# Bolt.net
KiCad netlist of a schematic drawn in EAGLE
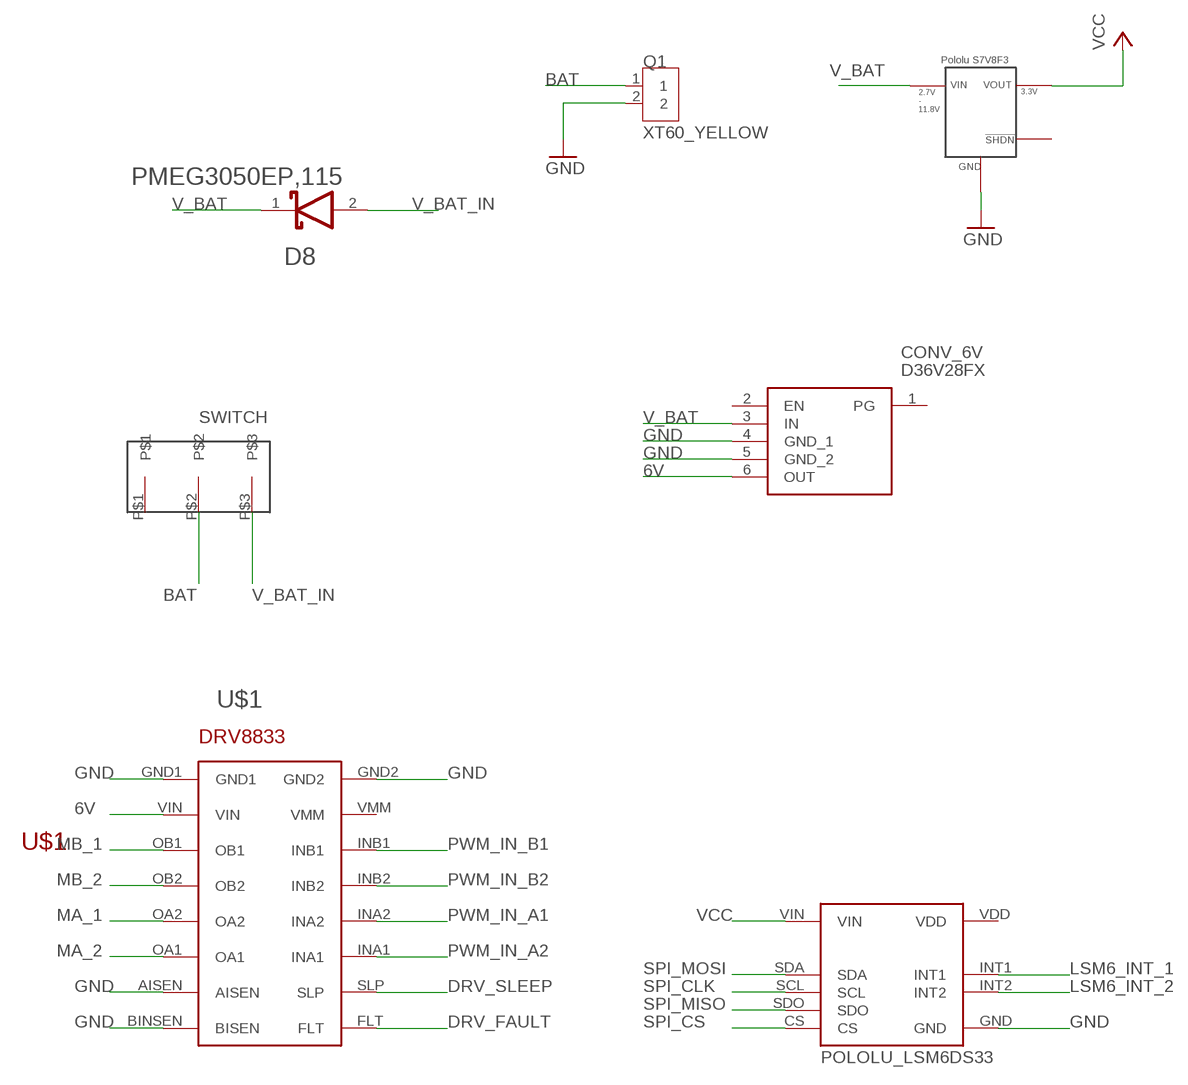
[diagram p0: schematic, sheet 1]
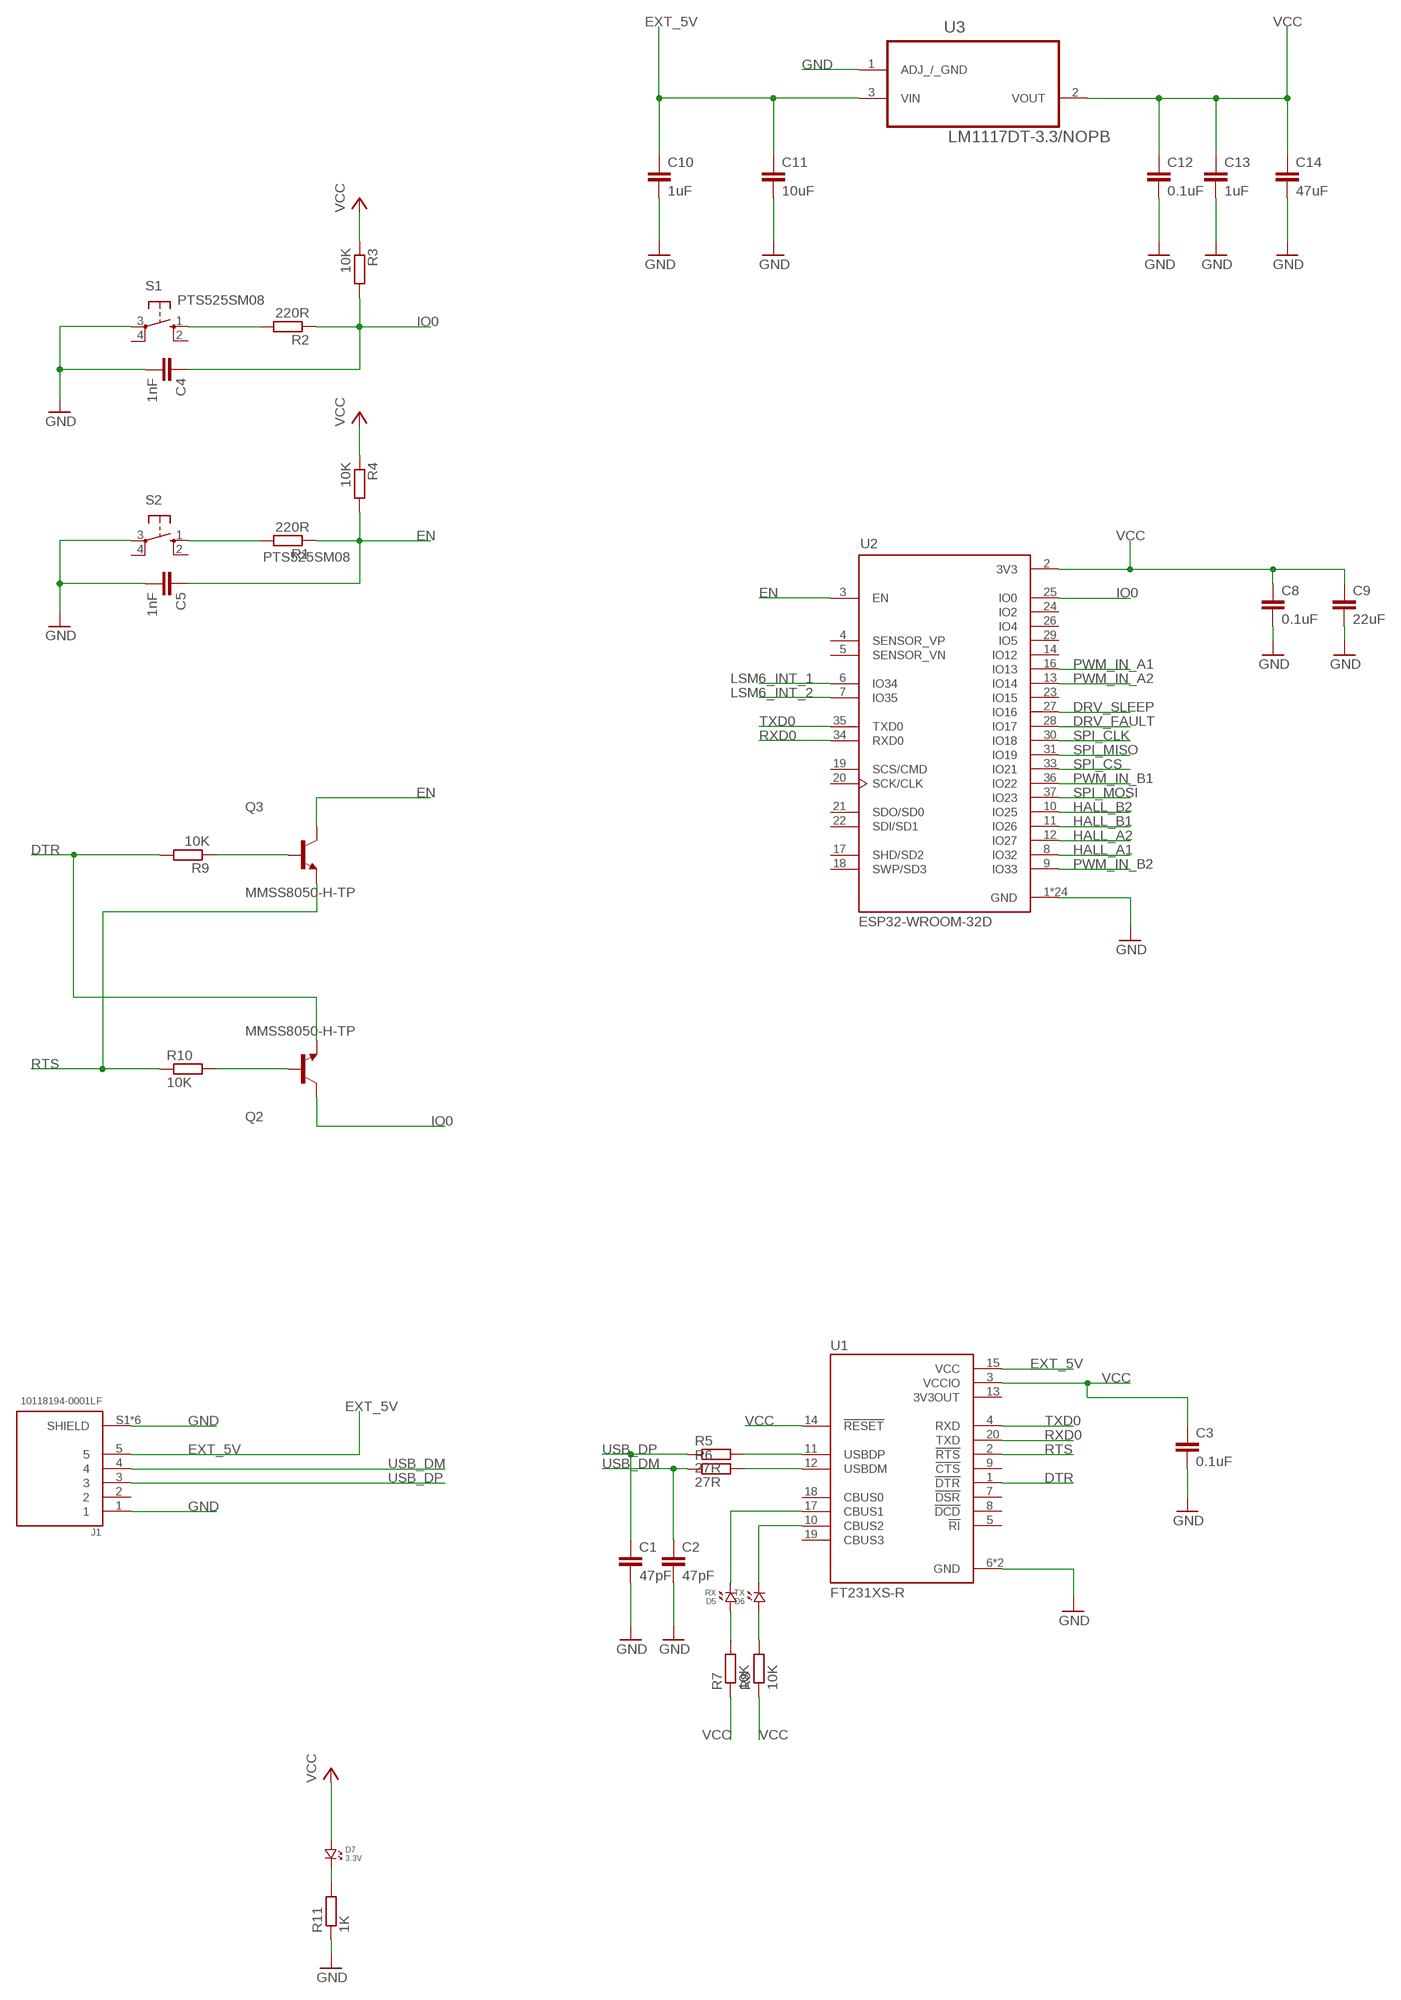
[diagram p1: schematic, sheet 2]
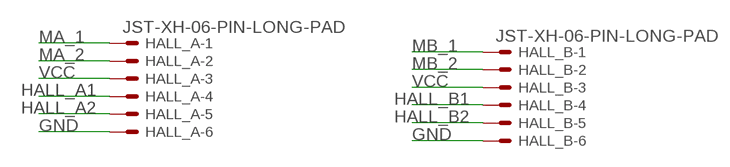
[diagram p2: schematic, sheet 3]

(export (version "E")
  (design (tool "Eeschema 10.0.6"))
  (components
    (comp (ref "HALL_A")
      (value "JST-XH-06-PIN-LONG-PAD")
      (footprint "eagle-import:JST-XH-06-PACKAGE-LONG-PAD")
      (libsource (lib "eagle-import") (part "JST-XH-06-PIN-LONG-PAD"))
    )
    (comp (ref "HALL_B")
      (value "JST-XH-06-PIN-LONG-PAD")
      (footprint "eagle-import:JST-XH-06-PACKAGE-LONG-PAD")
      (libsource (lib "eagle-import") (part "JST-XH-06-PIN-LONG-PAD"))
    )
    (comp (ref "CONV_3V3")
      (value "S7V8F3")
      (footprint "eagle-import:S7V8F3")
      (libsource (lib "eagle-import") (part "S7V8F3"))
    )
    (comp (ref "CONV_6V")
      (value "D36V28FX")
      (footprint "eagle-import:D36V28FX")
      (libsource (lib "eagle-import") (part "D36V28FX"))
    )
    (comp (ref "D8")
      (value "NEXPERIA_PMEG3050EP,115NEXPERIA_PMEG3050EP,115_0_0")
      (footprint "eagle-import:NEXPERIA_PMEG3050EP,115_0")
      (fields
        (field (name "DIGIKEY_PART_NUMBER") "1727-5317-1-ND")
        (field (name "MF") "Nexperia")
        (field (name "MOUSER_PART_NUMBER") "771-PMEG3050EP115")
      )
      (libsource (lib "eagle-import") (part "NEXPERIA_PMEG3050EP,115NEXPERIA_PMEG3050EP,115_0_0"))
    )
    (comp (ref "Q1")
      (value "XT60_YELLOW")
      (footprint "eagle-import:AMASS_XT60PB-M")
      (fields (field (name "MF") "Pololu") (field (name "MP") "XT60 YELLOW"))
      (libsource (lib "eagle-import") (part "XT60_YELLOW"))
    )
    (comp (ref "U$1")
      (value "POLOLU-DRV8833")
      (footprint "eagle-import:POLOLU-DRV8833")
      (libsource (lib "eagle-import") (part "POLOLU-DRV8833"))
    )
    (comp (ref "U$2")
      (value "POLOLU_LSM6DS33")
      (footprint "eagle-import:POLOLU_LSM6DS33")
      (libsource (lib "eagle-import") (part "POLOLU_LSM6DS33"))
    )
    (comp (ref "U$3")
      (value "SWITCH")
      (footprint "eagle-import:SWITCH")
      (libsource (lib "eagle-import") (part "SWITCH"))
    )
    (comp (ref "C1")
      (value "47pF")
      (footprint "eagle-import:C0805K")
      (libsource (lib "eagle-import") (part "C-EUC0805K"))
    )
    (comp (ref "C2")
      (value "47pF")
      (footprint "eagle-import:C0805K")
      (libsource (lib "eagle-import") (part "C-EUC0805K"))
    )
    (comp (ref "C3")
      (value "0.1uF")
      (footprint "eagle-import:C0805K")
      (libsource (lib "eagle-import") (part "C-EUC0805K"))
    )
    (comp (ref "C4")
      (value "1nF")
      (footprint "eagle-import:C0805K")
      (libsource (lib "eagle-import") (part "C-EUC0805K"))
    )
    (comp (ref "C5")
      (value "1nF")
      (footprint "eagle-import:C0805K")
      (libsource (lib "eagle-import") (part "C-EUC0805K"))
    )
    (comp (ref "C8")
      (value "0.1uF")
      (footprint "eagle-import:C0805K")
      (libsource (lib "eagle-import") (part "C-EUC0805K"))
    )
    (comp (ref "C9")
      (value "22uF")
      (footprint "eagle-import:C0805K")
      (libsource (lib "eagle-import") (part "C-EUC0805K"))
    )
    (comp (ref "C10")
      (value "1uF")
      (footprint "eagle-import:C0805K")
      (libsource (lib "eagle-import") (part "C-EUC0805K"))
    )
    (comp (ref "C11")
      (value "10uF")
      (footprint "eagle-import:C0805K")
      (libsource (lib "eagle-import") (part "C-EUC0805K"))
    )
    (comp (ref "C12")
      (value "0.1uF")
      (footprint "eagle-import:C0805K")
      (libsource (lib "eagle-import") (part "C-EUC0805K"))
    )
    (comp (ref "C13")
      (value "1uF")
      (footprint "eagle-import:C0805K")
      (libsource (lib "eagle-import") (part "C-EUC0805K"))
    )
    (comp (ref "C14")
      (value "47uF")
      (footprint "eagle-import:C0805K")
      (libsource (lib "eagle-import") (part "C-EUC0805K"))
    )
    (comp (ref "D5")
      (value "RX")
      (footprint "eagle-import:0805.LED")
      (libsource (lib "eagle-import") (part "LED.0805"))
    )
    (comp (ref "D6")
      (value "TX")
      (footprint "eagle-import:0805.LED")
      (libsource (lib "eagle-import") (part "LED.0805"))
    )
    (comp (ref "D7")
      (value "3.3V")
      (footprint "eagle-import:0805.LED")
      (libsource (lib "eagle-import") (part "LED.0805"))
    )
    (comp (ref "J1")
      (value "10118194-0001LF")
      (footprint "eagle-import:AMPHENOL_10118194-0001LF")
      (fields (field (name "MF") "Amphenol ICC (FCI)"))
      (libsource (lib "eagle-import") (part "10118194-0001LF"))
    )
    (comp (ref "Q2")
      (value "MMSS8050-H-TP")
      (footprint "eagle-import:TRANS_MMSS8050-H-TP")
      (fields (field (name "MF") "Micro Commercial"))
      (libsource (lib "eagle-import") (part "MMSS8050-H-TP"))
    )
    (comp (ref "Q3")
      (value "MMSS8050-H-TP")
      (footprint "eagle-import:TRANS_MMSS8050-H-TP")
      (fields (field (name "MF") "Micro Commercial"))
      (libsource (lib "eagle-import") (part "MMSS8050-H-TP"))
    )
    (comp (ref "R1")
      (value "220R")
      (footprint "eagle-import:R0805")
      (libsource (lib "eagle-import") (part "R-EU_R0805"))
    )
    (comp (ref "R2")
      (value "220R")
      (footprint "eagle-import:R0805")
      (libsource (lib "eagle-import") (part "R-EU_R0805"))
    )
    (comp (ref "R3")
      (value "10K")
      (footprint "eagle-import:R0805")
      (libsource (lib "eagle-import") (part "R-EU_R0805"))
    )
    (comp (ref "R4")
      (value "10K")
      (footprint "eagle-import:R0805")
      (libsource (lib "eagle-import") (part "R-EU_R0805"))
    )
    (comp (ref "R5")
      (value "27R")
      (footprint "eagle-import:R0805")
      (libsource (lib "eagle-import") (part "R-EU_R0805"))
    )
    (comp (ref "R6")
      (value "27R")
      (footprint "eagle-import:R0805")
      (libsource (lib "eagle-import") (part "R-EU_R0805"))
    )
    (comp (ref "R7")
      (value "10K")
      (footprint "eagle-import:R0805")
      (libsource (lib "eagle-import") (part "R-EU_R0805"))
    )
    (comp (ref "R8")
      (value "10K")
      (footprint "eagle-import:R0805")
      (libsource (lib "eagle-import") (part "R-EU_R0805"))
    )
    (comp (ref "R9")
      (value "10K")
      (footprint "eagle-import:R0805")
      (libsource (lib "eagle-import") (part "R-EU_R0805"))
    )
    (comp (ref "R10")
      (value "10K")
      (footprint "eagle-import:R0805")
      (libsource (lib "eagle-import") (part "R-EU_R0805"))
    )
    (comp (ref "R11")
      (value "1K")
      (footprint "eagle-import:R0805")
      (libsource (lib "eagle-import") (part "R-EU_R0805"))
    )
    (comp (ref "S1")
      (value "PTS525SM08")
      (footprint "eagle-import:SM08")
      (fields (field (name "MF") "C&K Components") (field (name "MPN") "PTS525SM08SMTR2LFS"))
      (libsource (lib "eagle-import") (part "PTS52508SM"))
    )
    (comp (ref "S2")
      (value "PTS525SM08")
      (footprint "eagle-import:SM08")
      (fields (field (name "MF") "C&K Components") (field (name "MPN") "PTS525SM08SMTR2LFS"))
      (libsource (lib "eagle-import") (part "PTS52508SM"))
    )
    (comp (ref "U1")
      (value "FT231XS-R")
      (footprint "eagle-import:SOP63P599X175-20N")
      (fields (field (name "DIGI-KEY_PART_NUMBER") "768-1129-1-ND") (field (name "MF") "FTDI,"))
      (libsource (lib "eagle-import") (part "FT231XS-R"))
    )
    (comp (ref "U2")
      (value "ESP32-WROOM-32D")
      (footprint "eagle-import:MODULE_ESP32-WROOM-32D")
      (fields (field (name "MF") "Espressif Systems"))
      (libsource (lib "eagle-import") (part "ESP32-WROOM-32D"))
    )
    (comp (ref "U3")
      (value "LM1117DT-3.3/NOPB")
      (footprint "eagle-import:TO228P970X238-3N")
      (fields (field (name "MF") "Texas Instruments"))
      (libsource (lib "eagle-import") (part "LM1117DT-3.3/NOPB"))
    )
  )
  (nets
    (net (code "1") (name "3V3OUT") (class "Default")
      (node (ref "U1") (pin "13") (pinfunction "3V3OUT_13") (pintype "power_in"))
    )
    (net (code "2") (name "6V") (class "Default")
      (node (ref "CONV_6V") (pin "6") (pinfunction "OUT_6") (pintype "bidirectional"))
      (node (ref "U$1") (pin "VIN") (pinfunction "VIN_VIN") (pintype "bidirectional"))
    )
    (net (code "3") (name "BAT") (class "Default")
      (node (ref "Q1") (pin "1") (pinfunction "1_1") (pintype "passive"))
      (node (ref "U$3") (pin "P$2") (pinfunction "P$2_P$2") (pintype "bidirectional"))
    )
    (net (code "4") (name "DRV_FAULT") (class "Default")
      (node (ref "U$1") (pin "FLT") (pinfunction "FLT_FLT") (pintype "bidirectional"))
      (node (ref "U2") (pin "28") (pinfunction "IO17_28") (pintype "bidirectional"))
    )
    (net (code "5") (name "DRV_SLEEP") (class "Default")
      (node (ref "U$1") (pin "SLP") (pinfunction "SLP_SLP") (pintype "bidirectional"))
      (node (ref "U2") (pin "27") (pinfunction "IO16_27") (pintype "bidirectional"))
    )
    (net (code "6") (name "DTR") (class "Default")
      (node (ref "Q2") (pin "2") (pinfunction "E_2") (pintype "passive"))
      (node (ref "R9") (pin "2") (pinfunction "2_2") (pintype "passive"))
      (node (ref "U1") (pin "1") (pinfunction "~{DTR}_1") (pintype "output"))
    )
    (net (code "7") (name "EN") (class "Default")
      (node (ref "C5") (pin "1") (pinfunction "1_1") (pintype "passive"))
      (node (ref "Q3") (pin "3") (pinfunction "C_3") (pintype "passive"))
      (node (ref "R1") (pin "1") (pinfunction "1_1") (pintype "passive"))
      (node (ref "R4") (pin "2") (pinfunction "2_2") (pintype "passive"))
      (node (ref "U2") (pin "3") (pinfunction "EN_3") (pintype "input"))
    )
    (net (code "8") (name "EXT_5V") (class "Default")
      (node (ref "C10") (pin "1") (pinfunction "1_1") (pintype "passive"))
      (node (ref "C11") (pin "1") (pinfunction "1_1") (pintype "passive"))
      (node (ref "J1") (pin "5") (pinfunction "5_5") (pintype "passive"))
      (node (ref "U1") (pin "15") (pinfunction "VCC_15") (pintype "power_in"))
      (node (ref "U3") (pin "3") (pinfunction "VIN_3") (pintype "input"))
    )
    (net (code "9") (name "GND") (class "Default")
      (node (ref "C1") (pin "2") (pinfunction "2_2") (pintype "passive"))
      (node (ref "C10") (pin "2") (pinfunction "2_2") (pintype "passive"))
      (node (ref "C11") (pin "2") (pinfunction "2_2") (pintype "passive"))
      (node (ref "C12") (pin "2") (pinfunction "2_2") (pintype "passive"))
      (node (ref "C13") (pin "2") (pinfunction "2_2") (pintype "passive"))
      (node (ref "C14") (pin "2") (pinfunction "2_2") (pintype "passive"))
      (node (ref "C2") (pin "2") (pinfunction "2_2") (pintype "passive"))
      (node (ref "C3") (pin "2") (pinfunction "2_2") (pintype "passive"))
      (node (ref "C4") (pin "2") (pinfunction "2_2") (pintype "passive"))
      (node (ref "C5") (pin "2") (pinfunction "2_2") (pintype "passive"))
      (node (ref "C8") (pin "2") (pinfunction "2_2") (pintype "passive"))
      (node (ref "C9") (pin "2") (pinfunction "2_2") (pintype "passive"))
      (node (ref "CONV_3V3") (pin "GND") (pinfunction "GND_GND") (pintype "bidirectional"))
      (node (ref "CONV_6V") (pin "4") (pinfunction "GND_1_4") (pintype "bidirectional"))
      (node (ref "CONV_6V") (pin "5") (pinfunction "GND_2_5") (pintype "bidirectional"))
      (node (ref "HALL_A") (pin "6") (pinfunction "S_6") (pintype "passive"))
      (node (ref "HALL_B") (pin "6") (pinfunction "S_6") (pintype "passive"))
      (node (ref "J1") (pin "1") (pinfunction "1_1") (pintype "passive"))
      (node (ref "J1") (pin "S1") (pinfunction "SHIELD_S1") (pintype "passive"))
      (node (ref "J1") (pin "S2") (pinfunction "SHIELD_S2") (pintype "passive"))
      (node (ref "J1") (pin "S3") (pinfunction "SHIELD_S3") (pintype "passive"))
      (node (ref "J1") (pin "S4") (pinfunction "SHIELD_S4") (pintype "passive"))
      (node (ref "J1") (pin "S5") (pinfunction "SHIELD_S5") (pintype "passive"))
      (node (ref "J1") (pin "S6") (pinfunction "SHIELD_S6") (pintype "passive"))
      (node (ref "Q1") (pin "2") (pinfunction "2_2") (pintype "passive"))
      (node (ref "R11") (pin "1") (pinfunction "1_1") (pintype "passive"))
      (node (ref "S1") (pin "3") (pinfunction "P_3") (pintype "passive"))
      (node (ref "S2") (pin "3") (pinfunction "P_3") (pintype "passive"))
      (node (ref "U$1") (pin "AISEN") (pinfunction "AISEN_AISEN") (pintype "bidirectional"))
      (node (ref "U$1") (pin "BINSEN") (pinfunction "BISEN_BINSEN") (pintype "bidirectional"))
      (node (ref "U$1") (pin "GND1") (pinfunction "GND1_GND1") (pintype "bidirectional"))
      (node (ref "U$1") (pin "GND2") (pinfunction "GND2_GND2") (pintype "bidirectional"))
      (node (ref "U$2") (pin "GND") (pinfunction "GND_GND") (pintype "bidirectional"))
      (node (ref "U1") (pin "16") (pinfunction "GND_16") (pintype "power_in"))
      (node (ref "U1") (pin "6") (pinfunction "GND_6") (pintype "power_in"))
      (node (ref "U2") (pin "1") (pinfunction "GND_1") (pintype "power_in"))
      (node (ref "U2") (pin "15") (pinfunction "GND_15") (pintype "power_in"))
      (node (ref "U2") (pin "38") (pinfunction "GND_38") (pintype "power_in"))
      (node (ref "U2") (pin "39_1") (pinfunction "GND_39_1") (pintype "power_in"))
      (node (ref "U2") (pin "39_10") (pinfunction "GND_39_10") (pintype "power_in"))
      (node (ref "U2") (pin "39_11") (pinfunction "GND_39_11") (pintype "power_in"))
      (node (ref "U2") (pin "39_12") (pinfunction "GND_39_12") (pintype "power_in"))
      (node (ref "U2") (pin "39_13") (pinfunction "GND_39_13") (pintype "power_in"))
      (node (ref "U2") (pin "39_14") (pinfunction "GND_39_14") (pintype "power_in"))
      (node (ref "U2") (pin "39_15") (pinfunction "GND_39_15") (pintype "power_in"))
      (node (ref "U2") (pin "39_16") (pinfunction "GND_39_16") (pintype "power_in"))
      (node (ref "U2") (pin "39_17") (pinfunction "GND_39_17") (pintype "power_in"))
      (node (ref "U2") (pin "39_18") (pinfunction "GND_39_18") (pintype "power_in"))
      (node (ref "U2") (pin "39_19") (pinfunction "GND_39_19") (pintype "power_in"))
      (node (ref "U2") (pin "39_2") (pinfunction "GND_39_2") (pintype "power_in"))
      (node (ref "U2") (pin "39_20") (pinfunction "GND_39_20") (pintype "power_in"))
      (node (ref "U2") (pin "39_21") (pinfunction "GND_39_21") (pintype "power_in"))
      (node (ref "U2") (pin "39_3") (pinfunction "GND_39_3") (pintype "power_in"))
      (node (ref "U2") (pin "39_4") (pinfunction "GND_39_4") (pintype "power_in"))
      (node (ref "U2") (pin "39_5") (pinfunction "GND_39_5") (pintype "power_in"))
      (node (ref "U2") (pin "39_6") (pinfunction "GND_39_6") (pintype "power_in"))
      (node (ref "U2") (pin "39_7") (pinfunction "GND_39_7") (pintype "power_in"))
      (node (ref "U2") (pin "39_8") (pinfunction "GND_39_8") (pintype "power_in"))
      (node (ref "U2") (pin "39_9") (pinfunction "GND_39_9") (pintype "power_in"))
      (node (ref "U3") (pin "1") (pinfunction "ADJ_/_GND_1") (pintype "power_in"))
    )
    (net (code "10") (name "HALL_A1") (class "Default")
      (node (ref "HALL_A") (pin "4") (pinfunction "S_4") (pintype "passive"))
      (node (ref "U2") (pin "8") (pinfunction "IO32_8") (pintype "bidirectional"))
    )
    (net (code "11") (name "HALL_A2") (class "Default")
      (node (ref "HALL_A") (pin "5") (pinfunction "S_5") (pintype "passive"))
      (node (ref "U2") (pin "12") (pinfunction "IO27_12") (pintype "bidirectional"))
    )
    (net (code "12") (name "HALL_B1") (class "Default")
      (node (ref "HALL_B") (pin "4") (pinfunction "S_4") (pintype "passive"))
      (node (ref "U2") (pin "11") (pinfunction "IO26_11") (pintype "bidirectional"))
    )
    (net (code "13") (name "HALL_B2") (class "Default")
      (node (ref "HALL_B") (pin "5") (pinfunction "S_5") (pintype "passive"))
      (node (ref "U2") (pin "10") (pinfunction "IO25_10") (pintype "bidirectional"))
    )
    (net (code "14") (name "IO0") (class "Default")
      (node (ref "C4") (pin "1") (pinfunction "1_1") (pintype "passive"))
      (node (ref "Q2") (pin "3") (pinfunction "C_3") (pintype "passive"))
      (node (ref "R2") (pin "1") (pinfunction "1_1") (pintype "passive"))
      (node (ref "R3") (pin "2") (pinfunction "2_2") (pintype "passive"))
      (node (ref "U2") (pin "25") (pinfunction "IO0_25") (pintype "bidirectional"))
    )
    (net (code "15") (name "LSM6_INT_1") (class "Default")
      (node (ref "U$2") (pin "INT1") (pinfunction "INT1_INT1") (pintype "bidirectional"))
      (node (ref "U2") (pin "6") (pinfunction "IO34_6") (pintype "input"))
    )
    (net (code "16") (name "LSM6_INT_2") (class "Default")
      (node (ref "U$2") (pin "INT2") (pinfunction "INT2_INT2") (pintype "bidirectional"))
      (node (ref "U2") (pin "7") (pinfunction "IO35_7") (pintype "input"))
    )
    (net (code "17") (name "MA_1") (class "Default")
      (node (ref "HALL_A") (pin "1") (pinfunction "S_1") (pintype "passive"))
      (node (ref "U$1") (pin "OA2") (pinfunction "OA2_OA2") (pintype "bidirectional"))
    )
    (net (code "18") (name "MA_2") (class "Default")
      (node (ref "HALL_A") (pin "2") (pinfunction "S_2") (pintype "passive"))
      (node (ref "U$1") (pin "OA1") (pinfunction "OA1_OA1") (pintype "bidirectional"))
    )
    (net (code "19") (name "MB_1") (class "Default")
      (node (ref "HALL_B") (pin "1") (pinfunction "S_1") (pintype "passive"))
      (node (ref "U$1") (pin "OB1") (pinfunction "OB1_OB1") (pintype "bidirectional"))
    )
    (net (code "20") (name "MB_2") (class "Default")
      (node (ref "HALL_B") (pin "2") (pinfunction "S_2") (pintype "passive"))
      (node (ref "U$1") (pin "OB2") (pinfunction "OB2_OB2") (pintype "bidirectional"))
    )
    (net (code "21") (name "Net-(D5-1)") (class "Default")
      (node (ref "D5") (pin "P$1") (pinfunction "1_P$1") (pintype "bidirectional"))
      (node (ref "R7") (pin "2") (pinfunction "2_2") (pintype "passive"))
    )
    (net (code "22") (name "Net-(D5-2)") (class "Default")
      (node (ref "D5") (pin "P$2") (pinfunction "2_P$2") (pintype "bidirectional"))
      (node (ref "U1") (pin "17") (pinfunction "CBUS1_17") (pintype "bidirectional"))
    )
    (net (code "23") (name "Net-(D6-1)") (class "Default")
      (node (ref "D6") (pin "P$1") (pinfunction "1_P$1") (pintype "bidirectional"))
      (node (ref "R8") (pin "2") (pinfunction "2_2") (pintype "passive"))
    )
    (net (code "24") (name "Net-(D6-2)") (class "Default")
      (node (ref "D6") (pin "P$2") (pinfunction "2_P$2") (pintype "bidirectional"))
      (node (ref "U1") (pin "10") (pinfunction "CBUS2_10") (pintype "bidirectional"))
    )
    (net (code "25") (name "Net-(D7-2)") (class "Default")
      (node (ref "D7") (pin "P$2") (pinfunction "2_P$2") (pintype "bidirectional"))
      (node (ref "R11") (pin "2") (pinfunction "2_2") (pintype "passive"))
    )
    (net (code "26") (name "Net-(Q2-B)") (class "Default")
      (node (ref "Q2") (pin "1") (pinfunction "B_1") (pintype "passive"))
      (node (ref "R10") (pin "2") (pinfunction "2_2") (pintype "passive"))
    )
    (net (code "27") (name "Net-(Q3-B)") (class "Default")
      (node (ref "Q3") (pin "1") (pinfunction "B_1") (pintype "passive"))
      (node (ref "R9") (pin "1") (pinfunction "1_1") (pintype "passive"))
    )
    (net (code "28") (name "Net-(R1-Pad2)") (class "Default")
      (node (ref "R1") (pin "2") (pinfunction "2_2") (pintype "passive"))
      (node (ref "S2") (pin "1") (pinfunction "S_1") (pintype "passive"))
    )
    (net (code "29") (name "Net-(R2-Pad2)") (class "Default")
      (node (ref "R2") (pin "2") (pinfunction "2_2") (pintype "passive"))
      (node (ref "S1") (pin "1") (pinfunction "S_1") (pintype "passive"))
    )
    (net (code "30") (name "Net-(U1-USBDM)") (class "Default")
      (node (ref "R6") (pin "2") (pinfunction "2_2") (pintype "passive"))
      (node (ref "U1") (pin "12") (pinfunction "USBDM_12") (pintype "input"))
    )
    (net (code "31") (name "Net-(U1-USBDP)") (class "Default")
      (node (ref "R5") (pin "2") (pinfunction "2_2") (pintype "passive"))
      (node (ref "U1") (pin "11") (pinfunction "USBDP_11") (pintype "input"))
    )
    (net (code "32") (name "PWM_IN_A1") (class "Default")
      (node (ref "U$1") (pin "INA2") (pinfunction "INA2_INA2") (pintype "bidirectional"))
      (node (ref "U2") (pin "16") (pinfunction "IO13_16") (pintype "bidirectional"))
    )
    (net (code "33") (name "PWM_IN_A2") (class "Default")
      (node (ref "U$1") (pin "INA1") (pinfunction "INA1_INA1") (pintype "bidirectional"))
      (node (ref "U2") (pin "13") (pinfunction "IO14_13") (pintype "bidirectional"))
    )
    (net (code "34") (name "PWM_IN_B1") (class "Default")
      (node (ref "U$1") (pin "INB1") (pinfunction "INB1_INB1") (pintype "bidirectional"))
      (node (ref "U2") (pin "36") (pinfunction "IO22_36") (pintype "bidirectional"))
    )
    (net (code "35") (name "PWM_IN_B2") (class "Default")
      (node (ref "U$1") (pin "INB2") (pinfunction "INB2_INB2") (pintype "bidirectional"))
      (node (ref "U2") (pin "9") (pinfunction "IO33_9") (pintype "bidirectional"))
    )
    (net (code "36") (name "RTS") (class "Default")
      (node (ref "Q3") (pin "2") (pinfunction "E_2") (pintype "passive"))
      (node (ref "R10") (pin "1") (pinfunction "1_1") (pintype "passive"))
      (node (ref "U1") (pin "2") (pinfunction "~{RTS}_2") (pintype "output"))
    )
    (net (code "37") (name "RXD0") (class "Default")
      (node (ref "U1") (pin "20") (pinfunction "TXD_20") (pintype "output"))
      (node (ref "U2") (pin "34") (pinfunction "RXD0_34") (pintype "bidirectional"))
    )
    (net (code "38") (name "SPI_CLK") (class "Default")
      (node (ref "U$2") (pin "SCL") (pinfunction "SCL_SCL") (pintype "bidirectional"))
      (node (ref "U2") (pin "30") (pinfunction "IO18_30") (pintype "bidirectional"))
    )
    (net (code "39") (name "SPI_CS") (class "Default")
      (node (ref "U$2") (pin "CS") (pinfunction "CS_CS") (pintype "bidirectional"))
      (node (ref "U2") (pin "33") (pinfunction "IO21_33") (pintype "bidirectional"))
    )
    (net (code "40") (name "SPI_MISO") (class "Default")
      (node (ref "U$2") (pin "SDO") (pinfunction "SDO_SDO") (pintype "bidirectional"))
      (node (ref "U2") (pin "31") (pinfunction "IO19_31") (pintype "bidirectional"))
    )
    (net (code "41") (name "SPI_MOSI") (class "Default")
      (node (ref "U$2") (pin "SDA") (pinfunction "SDA_SDA") (pintype "bidirectional"))
      (node (ref "U2") (pin "37") (pinfunction "IO23_37") (pintype "bidirectional"))
    )
    (net (code "42") (name "TXD0") (class "Default")
      (node (ref "U1") (pin "4") (pinfunction "RXD_4") (pintype "input"))
      (node (ref "U2") (pin "35") (pinfunction "TXD0_35") (pintype "bidirectional"))
    )
    (net (code "43") (name "USB_DM") (class "Default")
      (node (ref "C2") (pin "1") (pinfunction "1_1") (pintype "passive"))
      (node (ref "J1") (pin "4") (pinfunction "4_4") (pintype "passive"))
      (node (ref "R6") (pin "1") (pinfunction "1_1") (pintype "passive"))
    )
    (net (code "44") (name "USB_DP") (class "Default")
      (node (ref "C1") (pin "1") (pinfunction "1_1") (pintype "passive"))
      (node (ref "J1") (pin "3") (pinfunction "3_3") (pintype "passive"))
      (node (ref "R5") (pin "1") (pinfunction "1_1") (pintype "passive"))
    )
    (net (code "45") (name "VCC") (class "Default")
      (node (ref "C12") (pin "1") (pinfunction "1_1") (pintype "passive"))
      (node (ref "C13") (pin "1") (pinfunction "1_1") (pintype "passive"))
      (node (ref "C14") (pin "1") (pinfunction "1_1") (pintype "passive"))
      (node (ref "C3") (pin "1") (pinfunction "1_1") (pintype "passive"))
      (node (ref "C8") (pin "1") (pinfunction "1_1") (pintype "passive"))
      (node (ref "C9") (pin "1") (pinfunction "1_1") (pintype "passive"))
      (node (ref "CONV_3V3") (pin "VOUT") (pinfunction "VOUT_VOUT") (pintype "bidirectional"))
      (node (ref "D7") (pin "P$1") (pinfunction "1_P$1") (pintype "bidirectional"))
      (node (ref "HALL_A") (pin "3") (pinfunction "S_3") (pintype "passive"))
      (node (ref "HALL_B") (pin "3") (pinfunction "S_3") (pintype "passive"))
      (node (ref "R3") (pin "1") (pinfunction "1_1") (pintype "passive"))
      (node (ref "R4") (pin "1") (pinfunction "1_1") (pintype "passive"))
      (node (ref "R7") (pin "1") (pinfunction "1_1") (pintype "passive"))
      (node (ref "R8") (pin "1") (pinfunction "1_1") (pintype "passive"))
      (node (ref "U$2") (pin "VIN") (pinfunction "VIN_VIN") (pintype "bidirectional"))
      (node (ref "U1") (pin "14") (pinfunction "~{RESET}_14") (pintype "input"))
      (node (ref "U1") (pin "3") (pinfunction "VCCIO_3") (pintype "power_in"))
      (node (ref "U2") (pin "2") (pinfunction "3V3_2") (pintype "power_in"))
      (node (ref "U3") (pin "2") (pinfunction "VOUT_2") (pintype "output"))
    )
    (net (code "46") (name "V_BAT") (class "Default")
      (node (ref "CONV_3V3") (pin "VIN") (pinfunction "VIN_VIN") (pintype "bidirectional"))
      (node (ref "CONV_6V") (pin "3") (pinfunction "IN_3") (pintype "bidirectional"))
      (node (ref "D8") (pin "1") (pinfunction "CATHODE_1") (pintype "passive"))
    )
    (net (code "47") (name "V_BAT_IN") (class "Default")
      (node (ref "D8") (pin "2") (pinfunction "ANODE_2") (pintype "passive"))
      (node (ref "U$3") (pin "P$3") (pinfunction "P$3_P$3") (pintype "bidirectional"))
    )
    (net (code "48") (name "unconnected-(CONV_3V3-~{SHDN}-Pad!SHDN)") (class "Default")
      (node (ref "CONV_3V3") (pin "!SHDN") (pinfunction "~{SHDN}_!SHDN") (pintype "bidirectional"))
    )
    (net (code "49") (name "unconnected-(CONV_6V-EN-Pad2)") (class "Default")
      (node (ref "CONV_6V") (pin "2") (pinfunction "EN_2") (pintype "bidirectional"))
    )
    (net (code "50") (name "unconnected-(CONV_6V-PG-Pad1)") (class "Default")
      (node (ref "CONV_6V") (pin "1") (pinfunction "PG_1") (pintype "bidirectional"))
    )
    (net (code "51") (name "unconnected-(J1-Pad2)") (class "Default")
      (node (ref "J1") (pin "2") (pinfunction "2_2") (pintype "passive"))
    )
    (net (code "52") (name "unconnected-(S1-P-Pad4)") (class "Default")
      (node (ref "S1") (pin "4") (pinfunction "P_4") (pintype "passive"))
    )
    (net (code "53") (name "unconnected-(S1-S-Pad2)") (class "Default")
      (node (ref "S1") (pin "2") (pinfunction "S_2") (pintype "passive"))
    )
    (net (code "54") (name "unconnected-(S2-P-Pad4)") (class "Default")
      (node (ref "S2") (pin "4") (pinfunction "P_4") (pintype "passive"))
    )
    (net (code "55") (name "unconnected-(S2-S-Pad2)") (class "Default")
      (node (ref "S2") (pin "2") (pinfunction "S_2") (pintype "passive"))
    )
    (net (code "56") (name "unconnected-(U$1-PadVMM)") (class "Default")
      (node (ref "U$1") (pin "VMM") (pinfunction "VMM_VMM") (pintype "output"))
    )
    (net (code "57") (name "unconnected-(U$2-PadVDD)") (class "Default")
      (node (ref "U$2") (pin "VDD") (pinfunction "VDD_VDD") (pintype "bidirectional"))
    )
    (net (code "58") (name "unconnected-(U$3-PadP$1)") (class "Default")
      (node (ref "U$3") (pin "P$1") (pinfunction "P$1_P$1") (pintype "bidirectional"))
    )
    (net (code "59") (name "unconnected-(U1-CBUS0-Pad18)") (class "Default")
      (node (ref "U1") (pin "18") (pinfunction "CBUS0_18") (pintype "bidirectional"))
    )
    (net (code "60") (name "unconnected-(U1-CBUS3-Pad19)") (class "Default")
      (node (ref "U1") (pin "19") (pinfunction "CBUS3_19") (pintype "bidirectional"))
    )
    (net (code "61") (name "unconnected-(U1-~{CTS}-Pad9)") (class "Default")
      (node (ref "U1") (pin "9") (pinfunction "~{CTS}_9") (pintype "input"))
    )
    (net (code "62") (name "unconnected-(U1-~{DCD}-Pad8)") (class "Default")
      (node (ref "U1") (pin "8") (pinfunction "~{DCD}_8") (pintype "input"))
    )
    (net (code "63") (name "unconnected-(U1-~{DSR}-Pad7)") (class "Default")
      (node (ref "U1") (pin "7") (pinfunction "~{DSR}_7") (pintype "input"))
    )
    (net (code "64") (name "unconnected-(U1-~{RI}-Pad5)") (class "Default")
      (node (ref "U1") (pin "5") (pinfunction "~{RI}_5") (pintype "input"))
    )
    (net (code "65") (name "unconnected-(U2-IO2-Pad24)") (class "Default")
      (node (ref "U2") (pin "24") (pinfunction "IO2_24") (pintype "bidirectional"))
    )
    (net (code "66") (name "unconnected-(U2-IO4-Pad26)") (class "Default")
      (node (ref "U2") (pin "26") (pinfunction "IO4_26") (pintype "bidirectional"))
    )
    (net (code "67") (name "unconnected-(U2-IO5-Pad29)") (class "Default")
      (node (ref "U2") (pin "29") (pinfunction "IO5_29") (pintype "bidirectional"))
    )
    (net (code "68") (name "unconnected-(U2-IO12-Pad14)") (class "Default")
      (node (ref "U2") (pin "14") (pinfunction "IO12_14") (pintype "bidirectional"))
    )
    (net (code "69") (name "unconnected-(U2-IO15-Pad23)") (class "Default")
      (node (ref "U2") (pin "23") (pinfunction "IO15_23") (pintype "bidirectional"))
    )
    (net (code "70") (name "unconnected-(U2-SCK{slash}CLK-Pad20)") (class "Default")
      (node (ref "U2") (pin "20") (pinfunction "SCK/CLK_20") (pintype "bidirectional"))
    )
    (net (code "71") (name "unconnected-(U2-SCS{slash}CMD-Pad19)") (class "Default")
      (node (ref "U2") (pin "19") (pinfunction "SCS/CMD_19") (pintype "bidirectional"))
    )
    (net (code "72") (name "unconnected-(U2-SDI{slash}SD1-Pad22)") (class "Default")
      (node (ref "U2") (pin "22") (pinfunction "SDI/SD1_22") (pintype "bidirectional"))
    )
    (net (code "73") (name "unconnected-(U2-SDO{slash}SD0-Pad21)") (class "Default")
      (node (ref "U2") (pin "21") (pinfunction "SDO/SD0_21") (pintype "bidirectional"))
    )
    (net (code "74") (name "unconnected-(U2-SENSOR_VN-Pad5)") (class "Default")
      (node (ref "U2") (pin "5") (pinfunction "SENSOR_VN_5") (pintype "input"))
    )
    (net (code "75") (name "unconnected-(U2-SENSOR_VP-Pad4)") (class "Default")
      (node (ref "U2") (pin "4") (pinfunction "SENSOR_VP_4") (pintype "input"))
    )
    (net (code "76") (name "unconnected-(U2-SHD{slash}SD2-Pad17)") (class "Default")
      (node (ref "U2") (pin "17") (pinfunction "SHD/SD2_17") (pintype "bidirectional"))
    )
    (net (code "77") (name "unconnected-(U2-SWP{slash}SD3-Pad18)") (class "Default")
      (node (ref "U2") (pin "18") (pinfunction "SWP/SD3_18") (pintype "bidirectional"))
    )
  )
)
